# controller.net
KiCad netlist of a schematic drawn in EAGLE
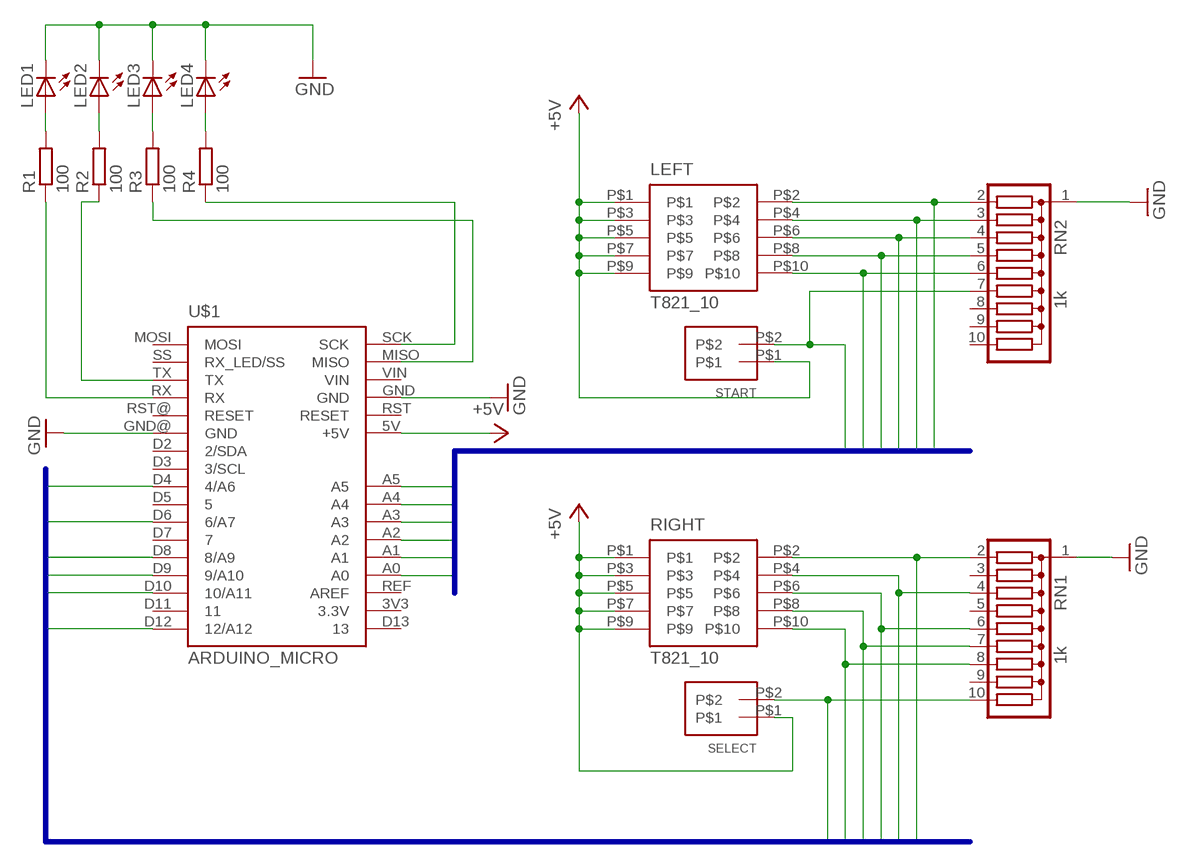
[diagram p0: schematic, sheet 1]

(export (version "E")
  (design (tool "Eeschema 10.0.6"))
  (components
    (comp (ref "LED1")
      (value "LED5MM")
      (footprint "eagle-import:LED5MM")
      (libsource (lib "eagle-import") (part "LED5MM"))
    )
    (comp (ref "LED2")
      (value "LED5MM")
      (footprint "eagle-import:LED5MM")
      (libsource (lib "eagle-import") (part "LED5MM"))
    )
    (comp (ref "LED3")
      (value "LED5MM")
      (footprint "eagle-import:LED5MM")
      (libsource (lib "eagle-import") (part "LED5MM"))
    )
    (comp (ref "LED4")
      (value "LED5MM")
      (footprint "eagle-import:LED5MM")
      (libsource (lib "eagle-import") (part "LED5MM"))
    )
    (comp (ref "LEFT")
      (value "T821_10")
      (footprint "eagle-import:T821_10")
      (libsource (lib "eagle-import") (part "T821_10"))
    )
    (comp (ref "R1")
      (value "100")
      (footprint "eagle-import:0204_7")
      (libsource (lib "eagle-import") (part "R-EU_0204/7"))
    )
    (comp (ref "R2")
      (value "100")
      (footprint "eagle-import:0204_7")
      (libsource (lib "eagle-import") (part "R-EU_0204/7"))
    )
    (comp (ref "R3")
      (value "100")
      (footprint "eagle-import:0204_7")
      (libsource (lib "eagle-import") (part "R-EU_0204/7"))
    )
    (comp (ref "R4")
      (value "100")
      (footprint "eagle-import:0204_7")
      (libsource (lib "eagle-import") (part "R-EU_0204/7"))
    )
    (comp (ref "RIGHT")
      (value "T821_10")
      (footprint "eagle-import:T821_10")
      (libsource (lib "eagle-import") (part "T821_10"))
    )
    (comp (ref "RN1")
      (value "1k")
      (footprint "eagle-import:SIL10")
      (libsource (lib "eagle-import") (part "G09R"))
    )
    (comp (ref "RN2")
      (value "1k")
      (footprint "eagle-import:SIL10")
      (libsource (lib "eagle-import") (part "G09R"))
    )
    (comp (ref "SELECT")
      (value "100MIL_2POS")
      (footprint "eagle-import:100MIL_2POS")
      (libsource (lib "eagle-import") (part "100MIL_2POS"))
    )
    (comp (ref "START")
      (value "100MIL_2POS")
      (footprint "eagle-import:100MIL_2POS")
      (libsource (lib "eagle-import") (part "100MIL_2POS"))
    )
    (comp (ref "U$1")
      (value "ARDUINO_MICRO")
      (footprint "eagle-import:ARDUINO_MICRO")
      (libsource (lib "eagle-import") (part "ARDUINO_MICRO"))
    )
  )
  (nets
    (net (code "1") (name "+5V") (class "Default")
      (node (ref "LEFT") (pin "P$1") (pinfunction "P$1_P$1") (pintype "bidirectional"))
      (node (ref "LEFT") (pin "P$3") (pinfunction "P$3_P$3") (pintype "bidirectional"))
      (node (ref "LEFT") (pin "P$5") (pinfunction "P$5_P$5") (pintype "bidirectional"))
      (node (ref "LEFT") (pin "P$7") (pinfunction "P$7_P$7") (pintype "bidirectional"))
      (node (ref "LEFT") (pin "P$9") (pinfunction "P$9_P$9") (pintype "bidirectional"))
      (node (ref "RIGHT") (pin "P$1") (pinfunction "P$1_P$1") (pintype "bidirectional"))
      (node (ref "RIGHT") (pin "P$3") (pinfunction "P$3_P$3") (pintype "bidirectional"))
      (node (ref "RIGHT") (pin "P$5") (pinfunction "P$5_P$5") (pintype "bidirectional"))
      (node (ref "RIGHT") (pin "P$7") (pinfunction "P$7_P$7") (pintype "bidirectional"))
      (node (ref "RIGHT") (pin "P$9") (pinfunction "P$9_P$9") (pintype "bidirectional"))
      (node (ref "SELECT") (pin "P$1") (pinfunction "P$1_P$1") (pintype "bidirectional"))
      (node (ref "START") (pin "P$1") (pinfunction "P$1_P$1") (pintype "bidirectional"))
      (node (ref "U$1") (pin "5V") (pinfunction "+5V_5V") (pintype "bidirectional"))
    )
    (net (code "2") (name "/B0") (class "Default")
      (node (ref "LEFT") (pin "P$2") (pinfunction "P$2_P$2") (pintype "bidirectional"))
      (node (ref "RN2") (pin "2") (pinfunction "2_2") (pintype "passive"))
      (node (ref "U$1") (pin "A0") (pinfunction "A0_A0") (pintype "bidirectional"))
    )
    (net (code "3") (name "/B1") (class "Default")
      (node (ref "LEFT") (pin "P$4") (pinfunction "P$4_P$4") (pintype "bidirectional"))
      (node (ref "RN2") (pin "3") (pinfunction "3_3") (pintype "passive"))
      (node (ref "U$1") (pin "A1") (pinfunction "A1_A1") (pintype "bidirectional"))
    )
    (net (code "4") (name "/B2") (class "Default")
      (node (ref "LEFT") (pin "P$6") (pinfunction "P$6_P$6") (pintype "bidirectional"))
      (node (ref "RN2") (pin "4") (pinfunction "4_4") (pintype "passive"))
      (node (ref "U$1") (pin "A2") (pinfunction "A2_A2") (pintype "bidirectional"))
    )
    (net (code "5") (name "/B3") (class "Default")
      (node (ref "LEFT") (pin "P$8") (pinfunction "P$8_P$8") (pintype "bidirectional"))
      (node (ref "RN2") (pin "5") (pinfunction "5_5") (pintype "passive"))
      (node (ref "U$1") (pin "A3") (pinfunction "A3_A3") (pintype "bidirectional"))
    )
    (net (code "6") (name "/B4") (class "Default")
      (node (ref "LEFT") (pin "P$10") (pinfunction "P$10_P$10") (pintype "bidirectional"))
      (node (ref "RN2") (pin "6") (pinfunction "6_6") (pintype "passive"))
      (node (ref "U$1") (pin "A4") (pinfunction "A4_A4") (pintype "bidirectional"))
    )
    (net (code "7") (name "/B5") (class "Default")
      (node (ref "RN2") (pin "7") (pinfunction "7_7") (pintype "passive"))
      (node (ref "START") (pin "P$2") (pinfunction "P$2_P$2") (pintype "bidirectional"))
      (node (ref "U$1") (pin "A5") (pinfunction "A5_A5") (pintype "bidirectional"))
    )
    (net (code "8") (name "/B6") (class "Default")
      (node (ref "RIGHT") (pin "P$2") (pinfunction "P$2_P$2") (pintype "bidirectional"))
      (node (ref "RN1") (pin "2") (pinfunction "2_2") (pintype "passive"))
      (node (ref "U$1") (pin "D4") (pinfunction "4/A6_D4") (pintype "bidirectional"))
    )
    (net (code "9") (name "/B7") (class "Default")
      (node (ref "RIGHT") (pin "P$4") (pinfunction "P$4_P$4") (pintype "bidirectional"))
      (node (ref "RN1") (pin "4") (pinfunction "4_4") (pintype "passive"))
      (node (ref "U$1") (pin "D6") (pinfunction "6/A7_D6") (pintype "bidirectional"))
    )
    (net (code "10") (name "/B8") (class "Default")
      (node (ref "RIGHT") (pin "P$6") (pinfunction "P$6_P$6") (pintype "bidirectional"))
      (node (ref "RN1") (pin "6") (pinfunction "6_6") (pintype "passive"))
      (node (ref "U$1") (pin "D8") (pinfunction "8/A9_D8") (pintype "bidirectional"))
    )
    (net (code "11") (name "/B9") (class "Default")
      (node (ref "RIGHT") (pin "P$8") (pinfunction "P$8_P$8") (pintype "bidirectional"))
      (node (ref "RN1") (pin "7") (pinfunction "7_7") (pintype "passive"))
      (node (ref "U$1") (pin "D9") (pinfunction "9/A10_D9") (pintype "bidirectional"))
    )
    (net (code "12") (name "/B10") (class "Default")
      (node (ref "RIGHT") (pin "P$10") (pinfunction "P$10_P$10") (pintype "bidirectional"))
      (node (ref "RN1") (pin "8") (pinfunction "8_8") (pintype "passive"))
      (node (ref "U$1") (pin "D10") (pinfunction "10/A11_D10") (pintype "bidirectional"))
    )
    (net (code "13") (name "/B11") (class "Default")
      (node (ref "RN1") (pin "10") (pinfunction "10_10") (pintype "passive"))
      (node (ref "SELECT") (pin "P$2") (pinfunction "P$2_P$2") (pintype "bidirectional"))
      (node (ref "U$1") (pin "D12") (pinfunction "12/A12_D12") (pintype "bidirectional"))
    )
    (net (code "14") (name "GND") (class "Default")
      (node (ref "LED1") (pin "K") (pinfunction "C_K") (pintype "passive"))
      (node (ref "LED2") (pin "K") (pinfunction "C_K") (pintype "passive"))
      (node (ref "LED3") (pin "K") (pinfunction "C_K") (pintype "passive"))
      (node (ref "LED4") (pin "K") (pinfunction "C_K") (pintype "passive"))
      (node (ref "RN1") (pin "1") (pinfunction "1_1") (pintype "passive"))
      (node (ref "RN2") (pin "1") (pinfunction "1_1") (pintype "passive"))
      (node (ref "U$1") (pin "GND") (pinfunction "GND_GND") (pintype "bidirectional"))
      (node (ref "U$1") (pin "GND@") (pinfunction "GND_GND@") (pintype "bidirectional"))
    )
    (net (code "15") (name "Net-(LED1-PadA)") (class "Default")
      (node (ref "LED1") (pin "A") (pinfunction "A_A") (pintype "passive"))
      (node (ref "R1") (pin "2") (pinfunction "2_2") (pintype "passive"))
    )
    (net (code "16") (name "Net-(LED2-PadA)") (class "Default")
      (node (ref "LED2") (pin "A") (pinfunction "A_A") (pintype "passive"))
      (node (ref "R2") (pin "2") (pinfunction "2_2") (pintype "passive"))
    )
    (net (code "17") (name "Net-(LED3-PadA)") (class "Default")
      (node (ref "LED3") (pin "A") (pinfunction "A_A") (pintype "passive"))
      (node (ref "R3") (pin "2") (pinfunction "2_2") (pintype "passive"))
    )
    (net (code "18") (name "Net-(LED4-PadA)") (class "Default")
      (node (ref "LED4") (pin "A") (pinfunction "A_A") (pintype "passive"))
      (node (ref "R4") (pin "2") (pinfunction "2_2") (pintype "passive"))
    )
    (net (code "19") (name "Net-(R1-Pad1)") (class "Default")
      (node (ref "R1") (pin "1") (pinfunction "1_1") (pintype "passive"))
      (node (ref "U$1") (pin "RX") (pinfunction "RX_RX") (pintype "bidirectional"))
    )
    (net (code "20") (name "Net-(R2-Pad1)") (class "Default")
      (node (ref "R2") (pin "1") (pinfunction "1_1") (pintype "passive"))
      (node (ref "U$1") (pin "TX") (pinfunction "TX_TX") (pintype "bidirectional"))
    )
    (net (code "21") (name "Net-(R3-Pad1)") (class "Default")
      (node (ref "R3") (pin "1") (pinfunction "1_1") (pintype "passive"))
      (node (ref "U$1") (pin "MISO") (pinfunction "MISO_MISO") (pintype "bidirectional"))
    )
    (net (code "22") (name "Net-(R4-Pad1)") (class "Default")
      (node (ref "R4") (pin "1") (pinfunction "1_1") (pintype "passive"))
      (node (ref "U$1") (pin "SCK") (pinfunction "SCK_SCK") (pintype "bidirectional"))
    )
    (net (code "23") (name "unconnected-(RN1-Pad3)") (class "Default")
      (node (ref "RN1") (pin "3") (pinfunction "3_3") (pintype "passive"))
    )
    (net (code "24") (name "unconnected-(RN1-Pad5)") (class "Default")
      (node (ref "RN1") (pin "5") (pinfunction "5_5") (pintype "passive"))
    )
    (net (code "25") (name "unconnected-(RN1-Pad9)") (class "Default")
      (node (ref "RN1") (pin "9") (pinfunction "9_9") (pintype "passive"))
    )
    (net (code "26") (name "unconnected-(RN2-Pad8)") (class "Default")
      (node (ref "RN2") (pin "8") (pinfunction "8_8") (pintype "passive"))
    )
    (net (code "27") (name "unconnected-(RN2-Pad9)") (class "Default")
      (node (ref "RN2") (pin "9") (pinfunction "9_9") (pintype "passive"))
    )
    (net (code "28") (name "unconnected-(RN2-Pad10)") (class "Default")
      (node (ref "RN2") (pin "10") (pinfunction "10_10") (pintype "passive"))
    )
    (net (code "29") (name "unconnected-(U$1-2{slash}SDA-PadD2)") (class "Default")
      (node (ref "U$1") (pin "D2") (pinfunction "2/SDA_D2") (pintype "bidirectional"))
    )
    (net (code "30") (name "unconnected-(U$1-3.3V-Pad3V3)") (class "Default")
      (node (ref "U$1") (pin "3V3") (pinfunction "3.3V_3V3") (pintype "bidirectional"))
    )
    (net (code "31") (name "unconnected-(U$1-3{slash}SCL-PadD3)") (class "Default")
      (node (ref "U$1") (pin "D3") (pinfunction "3/SCL_D3") (pintype "bidirectional"))
    )
    (net (code "32") (name "unconnected-(U$1-5-PadD5)") (class "Default")
      (node (ref "U$1") (pin "D5") (pinfunction "5_D5") (pintype "bidirectional"))
    )
    (net (code "33") (name "unconnected-(U$1-7-PadD7)") (class "Default")
      (node (ref "U$1") (pin "D7") (pinfunction "7_D7") (pintype "bidirectional"))
    )
    (net (code "34") (name "unconnected-(U$1-11-PadD11)") (class "Default")
      (node (ref "U$1") (pin "D11") (pinfunction "11_D11") (pintype "bidirectional"))
    )
    (net (code "35") (name "unconnected-(U$1-13-PadD13)") (class "Default")
      (node (ref "U$1") (pin "D13") (pinfunction "13_D13") (pintype "bidirectional"))
    )
    (net (code "36") (name "unconnected-(U$1-AREF-PadREF)") (class "Default")
      (node (ref "U$1") (pin "REF") (pinfunction "AREF_REF") (pintype "bidirectional"))
    )
    (net (code "37") (name "unconnected-(U$1-PadMOSI)") (class "Default")
      (node (ref "U$1") (pin "MOSI") (pinfunction "MOSI_MOSI") (pintype "bidirectional"))
    )
    (net (code "38") (name "unconnected-(U$1-PadVIN)") (class "Default")
      (node (ref "U$1") (pin "VIN") (pinfunction "VIN_VIN") (pintype "bidirectional"))
    )
    (net (code "39") (name "unconnected-(U$1-RESET-PadRST)") (class "Default")
      (node (ref "U$1") (pin "RST") (pinfunction "RESET_RST") (pintype "bidirectional"))
    )
    (net (code "40") (name "unconnected-(U$1-RESET-PadRST@)") (class "Default")
      (node (ref "U$1") (pin "RST@") (pinfunction "RESET_RST@") (pintype "bidirectional"))
    )
    (net (code "41") (name "unconnected-(U$1-RX_LED{slash}SS-PadSS)") (class "Default")
      (node (ref "U$1") (pin "SS") (pinfunction "RX_LED/SS_SS") (pintype "bidirectional"))
    )
  )
)
